# meetring_ic.net
KiCad netlist of a schematic drawn in EAGLE
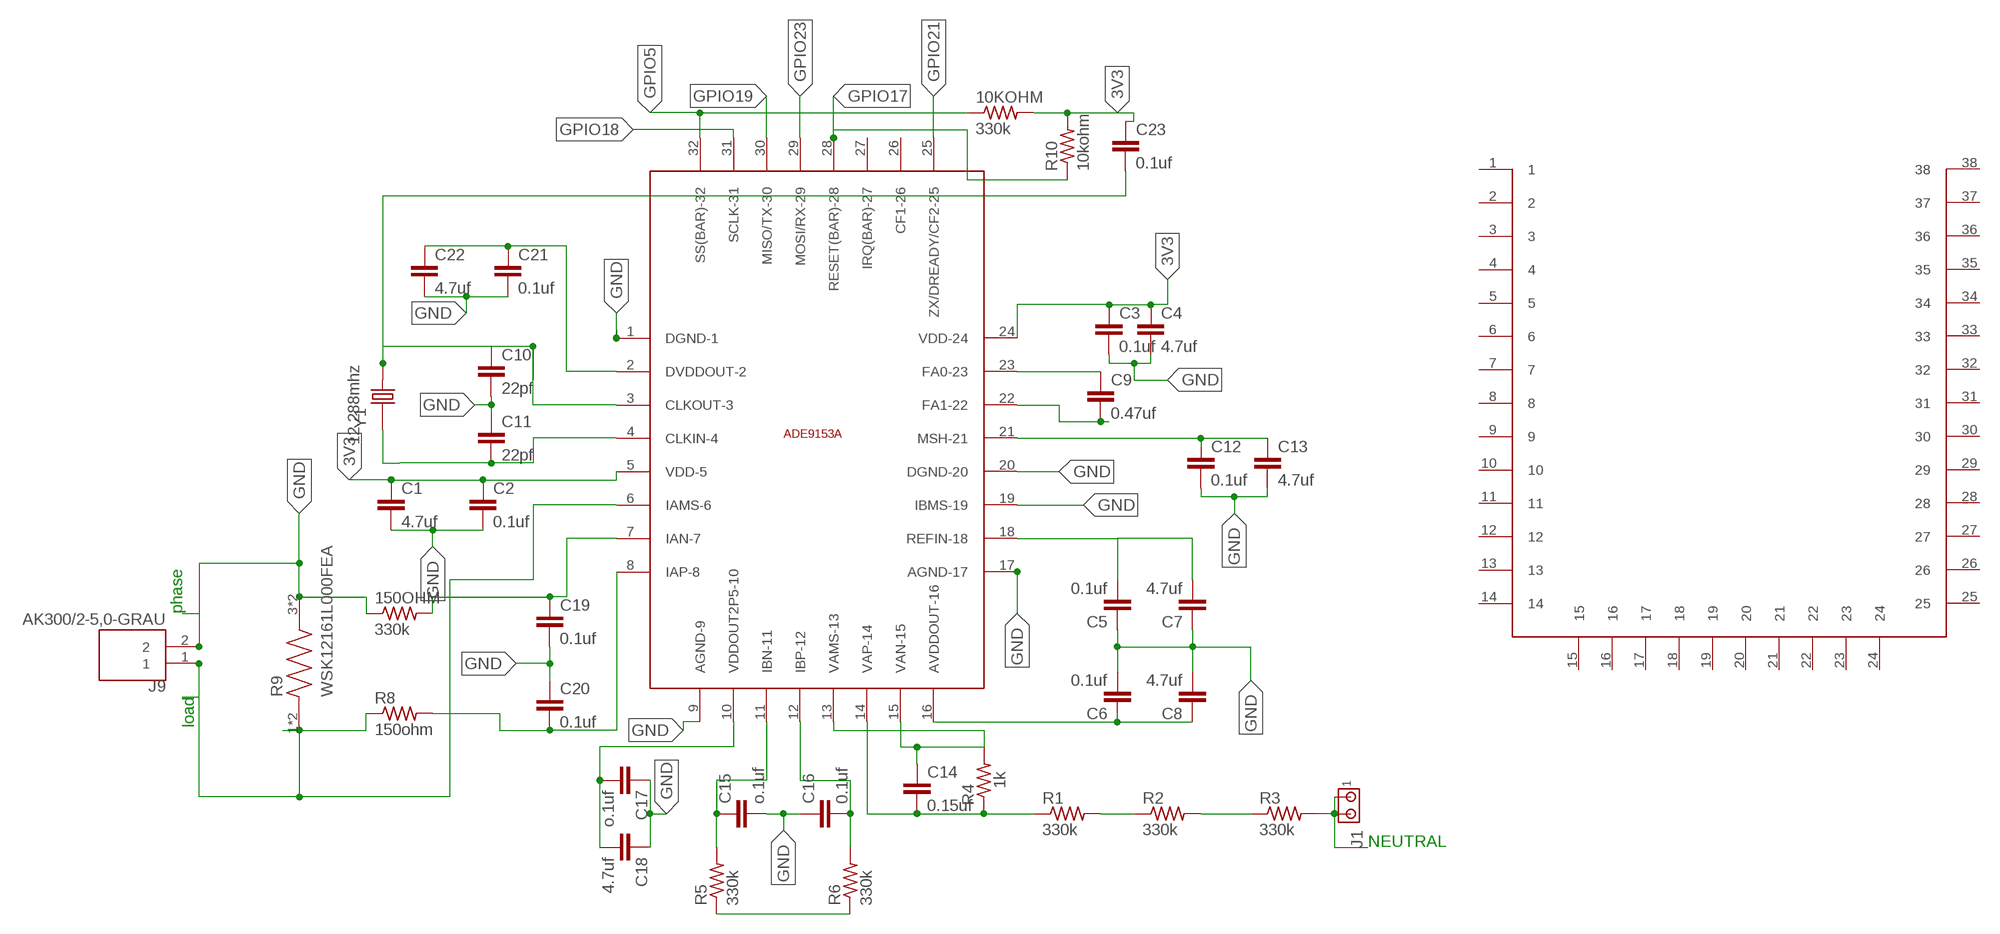
[diagram p0: schematic, sheet 1]

(export (version "E")
  (design (tool "Eeschema 10.0.6"))
  (components
    (comp (ref "10KOHM")
      (value "330k")
      (footprint "eagle-import:0204_7")
      (libsource (lib "eagle-import") (part "R-US_0204/7"))
    )
    (comp (ref "150OHM")
      (value "330k")
      (footprint "eagle-import:0204_7")
      (libsource (lib "eagle-import") (part "R-US_0204/7"))
    )
    (comp (ref "C1")
      (value "4.7uf")
      (footprint "eagle-import:C2.5-2")
      (libsource (lib "eagle-import") (part "C2.5/2"))
    )
    (comp (ref "C2")
      (value "0.1uf")
      (footprint "eagle-import:C2.5-2")
      (libsource (lib "eagle-import") (part "C2.5/2"))
    )
    (comp (ref "C3")
      (value "0.1uf")
      (footprint "eagle-import:C2.5-2")
      (libsource (lib "eagle-import") (part "C2.5/2"))
    )
    (comp (ref "C4")
      (value "4.7uf")
      (footprint "eagle-import:C2.5-2")
      (libsource (lib "eagle-import") (part "C2.5/2"))
    )
    (comp (ref "C5")
      (value "0.1uf")
      (footprint "eagle-import:C2.5-2")
      (libsource (lib "eagle-import") (part "C2.5/2"))
    )
    (comp (ref "C6")
      (value "0.1uf")
      (footprint "eagle-import:C2.5-2")
      (libsource (lib "eagle-import") (part "C2.5/2"))
    )
    (comp (ref "C7")
      (value "4.7uf")
      (footprint "eagle-import:C2.5-2")
      (libsource (lib "eagle-import") (part "C2.5/2"))
    )
    (comp (ref "C8")
      (value "4.7uf")
      (footprint "eagle-import:C2.5-2")
      (libsource (lib "eagle-import") (part "C2.5/2"))
    )
    (comp (ref "C9")
      (value "0.47uf")
      (footprint "eagle-import:C2.5-2")
      (libsource (lib "eagle-import") (part "C2.5/2"))
    )
    (comp (ref "C10")
      (value "22pf")
      (footprint "eagle-import:C2.5-2")
      (libsource (lib "eagle-import") (part "C2.5/2"))
    )
    (comp (ref "C11")
      (value "22pf")
      (footprint "eagle-import:C2.5-2")
      (libsource (lib "eagle-import") (part "C2.5/2"))
    )
    (comp (ref "C12")
      (value "0.1uf")
      (footprint "eagle-import:C2.5-2")
      (libsource (lib "eagle-import") (part "C2.5/2"))
    )
    (comp (ref "C13")
      (value "4.7uf")
      (footprint "eagle-import:C2.5-2")
      (libsource (lib "eagle-import") (part "C2.5/2"))
    )
    (comp (ref "C14")
      (value "0.15uf")
      (footprint "eagle-import:C2.5-2")
      (libsource (lib "eagle-import") (part "C2.5/2"))
    )
    (comp (ref "C15")
      (value "o.1uf")
      (footprint "eagle-import:C2.5-2")
      (libsource (lib "eagle-import") (part "C2.5/2"))
    )
    (comp (ref "C16")
      (value "0.1uf")
      (footprint "eagle-import:C2.5-2")
      (libsource (lib "eagle-import") (part "C2.5/2"))
    )
    (comp (ref "C17")
      (value "o.1uf")
      (footprint "eagle-import:C2.5-2")
      (libsource (lib "eagle-import") (part "C2.5/2"))
    )
    (comp (ref "C18")
      (value "4.7uf")
      (footprint "eagle-import:C2.5-2")
      (libsource (lib "eagle-import") (part "C2.5/2"))
    )
    (comp (ref "C19")
      (value "0.1uf")
      (footprint "eagle-import:C2.5-2")
      (libsource (lib "eagle-import") (part "C2.5/2"))
    )
    (comp (ref "C20")
      (value "0.1uf")
      (footprint "eagle-import:C2.5-2")
      (libsource (lib "eagle-import") (part "C2.5/2"))
    )
    (comp (ref "C21")
      (value "0.1uf")
      (footprint "eagle-import:C2.5-2")
      (libsource (lib "eagle-import") (part "C2.5/2"))
    )
    (comp (ref "C22")
      (value "4.7uf")
      (footprint "eagle-import:C2.5-2")
      (libsource (lib "eagle-import") (part "C2.5/2"))
    )
    (comp (ref "C23")
      (value "0.1uf")
      (footprint "eagle-import:C2.5-2")
      (libsource (lib "eagle-import") (part "C2.5/2"))
    )
    (comp (ref "J1")
      (value "MTA02-156")
      (footprint "eagle-import:1X2MTA")
      (libsource (lib "eagle-import") (part "MTA02-156"))
    )
    (comp (ref "J9")
      (value "AK300/2-5,0-GRAU")
      (footprint "eagle-import:PTR_AK300_2-5,0-GRAU")
      (fields (field (name "MF") "PTR Messtechnik"))
      (libsource (lib "eagle-import") (part "AK300/2-5,0-GRAU"))
    )
    (comp (ref "R1")
      (value "330k")
      (footprint "eagle-import:0204_7")
      (libsource (lib "eagle-import") (part "R-US_0204/7"))
    )
    (comp (ref "R2")
      (value "330k")
      (footprint "eagle-import:0204_7")
      (libsource (lib "eagle-import") (part "R-US_0204/7"))
    )
    (comp (ref "R3")
      (value "330k")
      (footprint "eagle-import:0204_7")
      (libsource (lib "eagle-import") (part "R-US_0204/7"))
    )
    (comp (ref "R4")
      (value "1k")
      (footprint "eagle-import:0204_7")
      (libsource (lib "eagle-import") (part "R-US_0204/7"))
    )
    (comp (ref "R5")
      (value "330k")
      (footprint "eagle-import:0204_7")
      (libsource (lib "eagle-import") (part "R-US_0204/7"))
    )
    (comp (ref "R6")
      (value "330k")
      (footprint "eagle-import:0204_7")
      (libsource (lib "eagle-import") (part "R-US_0204/7"))
    )
    (comp (ref "R8")
      (value "150ohm")
      (footprint "eagle-import:0204_7")
      (libsource (lib "eagle-import") (part "R-US_0204/7"))
    )
    (comp (ref "R9")
      (value "WSK12161L000FEA")
      (footprint "eagle-import:RES_WSK12161L000FEA")
      (fields (field (name "MF") "Vishay Intertechnology"))
      (libsource (lib "eagle-import") (part "WSK12161L000FEA"))
    )
    (comp (ref "R10")
      (value "10kohm")
      (footprint "eagle-import:0204_7")
      (libsource (lib "eagle-import") (part "R-US_0204/7"))
    )
    (comp (ref "U$1")
      (value "ADE9153A_BASEADE9153A_BASE")
      (footprint "eagle-import:ADE9153A_BASE")
      (libsource (lib "eagle-import") (part "ADE9153A_BASEADE9153A_BASE"))
    )
    (comp (ref "U$2")
      (value "LIB1OPTION_HOLE")
      (footprint "eagle-import:1X14MTA")
      (libsource (lib "eagle-import") (part "LIB1OPTION_HOLE"))
    )
    (comp (ref "Y1")
      (value "12.288mhz")
      (footprint "eagle-import:XTAL_ECS-200-20-1X")
      (fields (field (name "MF") "ECS International") (field (name "MP") "ECS-240.0001-18-1X"))
      (libsource (lib "eagle-import") (part "ECS-240.0001-18-1X"))
    )
  )
  (nets
    (net (code "1") (name "3V3") (class "Default")
      (node (ref "10KOHM") (pin "2") (pinfunction "2_2") (pintype "passive"))
      (node (ref "C1") (pin "1") (pinfunction "1_1") (pintype "passive"))
      (node (ref "C2") (pin "1") (pinfunction "1_1") (pintype "passive"))
      (node (ref "C23") (pin "1") (pinfunction "1_1") (pintype "passive"))
      (node (ref "C3") (pin "1") (pinfunction "1_1") (pintype "passive"))
      (node (ref "C4") (pin "1") (pinfunction "1_1") (pintype "passive"))
      (node (ref "R10") (pin "2") (pinfunction "2_2") (pintype "passive"))
      (node (ref "U$1") (pin "24") (pinfunction "VDD-24_24") (pintype "bidirectional"))
      (node (ref "U$1") (pin "5") (pinfunction "VDD-5_5") (pintype "bidirectional"))
    )
    (net (code "2") (name "GND") (class "Default")
      (node (ref "150OHM") (pin "1") (pinfunction "1_1") (pintype "passive"))
      (node (ref "C1") (pin "2") (pinfunction "2_2") (pintype "passive"))
      (node (ref "C10") (pin "2") (pinfunction "2_2") (pintype "passive"))
      (node (ref "C11") (pin "1") (pinfunction "1_1") (pintype "passive"))
      (node (ref "C12") (pin "2") (pinfunction "2_2") (pintype "passive"))
      (node (ref "C13") (pin "2") (pinfunction "2_2") (pintype "passive"))
      (node (ref "C15") (pin "2") (pinfunction "2_2") (pintype "passive"))
      (node (ref "C16") (pin "1") (pinfunction "1_1") (pintype "passive"))
      (node (ref "C17") (pin "1") (pinfunction "1_1") (pintype "passive"))
      (node (ref "C18") (pin "1") (pinfunction "1_1") (pintype "passive"))
      (node (ref "C19") (pin "2") (pinfunction "2_2") (pintype "passive"))
      (node (ref "C2") (pin "2") (pinfunction "2_2") (pintype "passive"))
      (node (ref "C20") (pin "1") (pinfunction "1_1") (pintype "passive"))
      (node (ref "C21") (pin "2") (pinfunction "2_2") (pintype "passive"))
      (node (ref "C22") (pin "2") (pinfunction "2_2") (pintype "passive"))
      (node (ref "C3") (pin "2") (pinfunction "2_2") (pintype "passive"))
      (node (ref "C4") (pin "2") (pinfunction "2_2") (pintype "passive"))
      (node (ref "C5") (pin "1") (pinfunction "1_1") (pintype "passive"))
      (node (ref "C6") (pin "2") (pinfunction "2_2") (pintype "passive"))
      (node (ref "C7") (pin "1") (pinfunction "1_1") (pintype "passive"))
      (node (ref "C8") (pin "2") (pinfunction "2_2") (pintype "passive"))
      (node (ref "J9") (pin "2") (pinfunction "2_2") (pintype "passive"))
      (node (ref "R9") (pin "3") (pinfunction "2_3") (pintype "passive"))
      (node (ref "R9") (pin "4") (pinfunction "2_4") (pintype "passive"))
      (node (ref "U$1") (pin "1") (pinfunction "DGND-1_1") (pintype "bidirectional"))
      (node (ref "U$1") (pin "17") (pinfunction "AGND-17_17") (pintype "bidirectional"))
      (node (ref "U$1") (pin "19") (pinfunction "IBMS-19_19") (pintype "bidirectional"))
      (node (ref "U$1") (pin "20") (pinfunction "DGND-20_20") (pintype "bidirectional"))
      (node (ref "U$1") (pin "9") (pinfunction "AGND-9_9") (pintype "bidirectional"))
    )
    (net (code "3") (name "GPIO5") (class "Default")
      (node (ref "10KOHM") (pin "1") (pinfunction "1_1") (pintype "passive"))
      (node (ref "U$1") (pin "32") (pinfunction "SS(BAR)-32_32") (pintype "bidirectional"))
    )
    (net (code "4") (name "GPIO17") (class "Default")
      (node (ref "R10") (pin "1") (pinfunction "1_1") (pintype "passive"))
      (node (ref "U$1") (pin "28") (pinfunction "RESET(BAR)-28_28") (pintype "bidirectional"))
    )
    (net (code "5") (name "GPIO18") (class "Default")
      (node (ref "U$1") (pin "31") (pinfunction "SCLK-31_31") (pintype "bidirectional"))
    )
    (net (code "6") (name "GPIO19") (class "Default")
      (node (ref "U$1") (pin "30") (pinfunction "MISO/TX-30_30") (pintype "bidirectional"))
    )
    (net (code "7") (name "GPIO21") (class "Default")
      (node (ref "U$1") (pin "25") (pinfunction "ZX/DREADY/CF2-25_25") (pintype "bidirectional"))
    )
    (net (code "8") (name "GPIO23") (class "Default")
      (node (ref "U$1") (pin "29") (pinfunction "MOSI/RX-29_29") (pintype "bidirectional"))
    )
    (net (code "9") (name "Net-(J1-Pad1)") (class "Default")
      (node (ref "J1") (pin "1") (pinfunction "1_1") (pintype "passive"))
      (node (ref "J1") (pin "2") (pinfunction "2_2") (pintype "passive"))
      (node (ref "R3") (pin "2") (pinfunction "2_2") (pintype "passive"))
    )
    (net (code "10") (name "Net-(R1-Pad2)") (class "Default")
      (node (ref "R1") (pin "2") (pinfunction "2_2") (pintype "passive"))
      (node (ref "R2") (pin "1") (pinfunction "1_1") (pintype "passive"))
    )
    (net (code "11") (name "Net-(R2-Pad2)") (class "Default")
      (node (ref "R2") (pin "2") (pinfunction "2_2") (pintype "passive"))
      (node (ref "R3") (pin "1") (pinfunction "1_1") (pintype "passive"))
    )
    (net (code "12") (name "Net-(R5-Pad1)") (class "Default")
      (node (ref "R5") (pin "1") (pinfunction "1_1") (pintype "passive"))
      (node (ref "R6") (pin "1") (pinfunction "1_1") (pintype "passive"))
    )
    (net (code "13") (name "Net-(U$1-AVDDOUT-16)") (class "Default")
      (node (ref "C6") (pin "1") (pinfunction "1_1") (pintype "passive"))
      (node (ref "C8") (pin "1") (pinfunction "1_1") (pintype "passive"))
      (node (ref "U$1") (pin "16") (pinfunction "AVDDOUT-16_16") (pintype "bidirectional"))
    )
    (net (code "14") (name "Net-(U$1-CLKIN-4)") (class "Default")
      (node (ref "C11") (pin "2") (pinfunction "2_2") (pintype "passive"))
      (node (ref "U$1") (pin "4") (pinfunction "CLKIN-4_4") (pintype "bidirectional"))
      (node (ref "Y1") (pin "1") (pinfunction "1_1") (pintype "passive"))
    )
    (net (code "15") (name "Net-(U$1-CLKOUT-3)") (class "Default")
      (node (ref "C10") (pin "1") (pinfunction "1_1") (pintype "passive"))
      (node (ref "C23") (pin "2") (pinfunction "2_2") (pintype "passive"))
      (node (ref "U$1") (pin "3") (pinfunction "CLKOUT-3_3") (pintype "bidirectional"))
      (node (ref "Y1") (pin "2") (pinfunction "2_2") (pintype "passive"))
    )
    (net (code "16") (name "Net-(U$1-DVDDOUT-2)") (class "Default")
      (node (ref "C21") (pin "1") (pinfunction "1_1") (pintype "passive"))
      (node (ref "C22") (pin "1") (pinfunction "1_1") (pintype "passive"))
      (node (ref "U$1") (pin "2") (pinfunction "DVDDOUT-2_2") (pintype "bidirectional"))
    )
    (net (code "17") (name "Net-(U$1-FA0-23)") (class "Default")
      (node (ref "C9") (pin "1") (pinfunction "1_1") (pintype "passive"))
      (node (ref "U$1") (pin "23") (pinfunction "FA0-23_23") (pintype "bidirectional"))
    )
    (net (code "18") (name "Net-(U$1-FA1-22)") (class "Default")
      (node (ref "C9") (pin "2") (pinfunction "2_2") (pintype "passive"))
      (node (ref "U$1") (pin "22") (pinfunction "FA1-22_22") (pintype "bidirectional"))
    )
    (net (code "19") (name "Net-(U$1-IAMS-6)") (class "Default")
      (node (ref "J9") (pin "1") (pinfunction "1_1") (pintype "passive"))
      (node (ref "R8") (pin "1") (pinfunction "1_1") (pintype "passive"))
      (node (ref "R9") (pin "1") (pinfunction "1_1") (pintype "passive"))
      (node (ref "R9") (pin "2") (pinfunction "1_2") (pintype "passive"))
      (node (ref "U$1") (pin "6") (pinfunction "IAMS-6_6") (pintype "bidirectional"))
    )
    (net (code "20") (name "Net-(U$1-IAN-7)") (class "Default")
      (node (ref "150OHM") (pin "2") (pinfunction "2_2") (pintype "passive"))
      (node (ref "C19") (pin "1") (pinfunction "1_1") (pintype "passive"))
      (node (ref "U$1") (pin "7") (pinfunction "IAN-7_7") (pintype "bidirectional"))
    )
    (net (code "21") (name "Net-(U$1-IAP-8)") (class "Default")
      (node (ref "C20") (pin "2") (pinfunction "2_2") (pintype "passive"))
      (node (ref "R8") (pin "2") (pinfunction "2_2") (pintype "passive"))
      (node (ref "U$1") (pin "8") (pinfunction "IAP-8_8") (pintype "bidirectional"))
    )
    (net (code "22") (name "Net-(U$1-IBN-11)") (class "Default")
      (node (ref "C15") (pin "1") (pinfunction "1_1") (pintype "passive"))
      (node (ref "R5") (pin "2") (pinfunction "2_2") (pintype "passive"))
      (node (ref "U$1") (pin "11") (pinfunction "IBN-11_11") (pintype "bidirectional"))
    )
    (net (code "23") (name "Net-(U$1-IBP-12)") (class "Default")
      (node (ref "C16") (pin "2") (pinfunction "2_2") (pintype "passive"))
      (node (ref "R6") (pin "2") (pinfunction "2_2") (pintype "passive"))
      (node (ref "U$1") (pin "12") (pinfunction "IBP-12_12") (pintype "bidirectional"))
    )
    (net (code "24") (name "Net-(U$1-MSH-21)") (class "Default")
      (node (ref "C12") (pin "1") (pinfunction "1_1") (pintype "passive"))
      (node (ref "C13") (pin "1") (pinfunction "1_1") (pintype "passive"))
      (node (ref "U$1") (pin "21") (pinfunction "MSH-21_21") (pintype "bidirectional"))
    )
    (net (code "25") (name "Net-(U$1-REFIN-18)") (class "Default")
      (node (ref "C5") (pin "2") (pinfunction "2_2") (pintype "passive"))
      (node (ref "C7") (pin "2") (pinfunction "2_2") (pintype "passive"))
      (node (ref "U$1") (pin "18") (pinfunction "REFIN-18_18") (pintype "bidirectional"))
    )
    (net (code "26") (name "Net-(U$1-VAMS-13)") (class "Default")
      (node (ref "C14") (pin "1") (pinfunction "1_1") (pintype "passive"))
      (node (ref "R4") (pin "2") (pinfunction "2_2") (pintype "passive"))
      (node (ref "U$1") (pin "13") (pinfunction "VAMS-13_13") (pintype "bidirectional"))
      (node (ref "U$1") (pin "15") (pinfunction "VAN-15_15") (pintype "bidirectional"))
    )
    (net (code "27") (name "Net-(U$1-VAP-14)") (class "Default")
      (node (ref "C14") (pin "2") (pinfunction "2_2") (pintype "passive"))
      (node (ref "R1") (pin "1") (pinfunction "1_1") (pintype "passive"))
      (node (ref "R4") (pin "1") (pinfunction "1_1") (pintype "passive"))
      (node (ref "U$1") (pin "14") (pinfunction "VAP-14_14") (pintype "bidirectional"))
    )
    (net (code "28") (name "Net-(U$1-VDDOUT2P5-10)") (class "Default")
      (node (ref "C17") (pin "2") (pinfunction "2_2") (pintype "passive"))
      (node (ref "C18") (pin "2") (pinfunction "2_2") (pintype "passive"))
      (node (ref "U$1") (pin "10") (pinfunction "VDDOUT2P5-10_10") (pintype "bidirectional"))
    )
    (net (code "29") (name "unconnected-(U$1-CF1-26-Pad26)") (class "Default")
      (node (ref "U$1") (pin "26") (pinfunction "CF1-26_26") (pintype "bidirectional"))
    )
    (net (code "30") (name "unconnected-(U$1-IRQ(BAR)-27-Pad27)") (class "Default")
      (node (ref "U$1") (pin "27") (pinfunction "IRQ(BAR)-27_27") (pintype "bidirectional"))
    )
    (net (code "31") (name "unconnected-(U$2-Pad1)") (class "Default")
      (node (ref "U$2") (pin "1") (pinfunction "1_1") (pintype "bidirectional"))
    )
    (net (code "32") (name "unconnected-(U$2-Pad2)") (class "Default")
      (node (ref "U$2") (pin "2") (pinfunction "2_2") (pintype "bidirectional"))
    )
    (net (code "33") (name "unconnected-(U$2-Pad3)") (class "Default")
      (node (ref "U$2") (pin "3") (pinfunction "3_3") (pintype "bidirectional"))
    )
    (net (code "34") (name "unconnected-(U$2-Pad4)") (class "Default")
      (node (ref "U$2") (pin "4") (pinfunction "4_4") (pintype "bidirectional"))
    )
    (net (code "35") (name "unconnected-(U$2-Pad5)") (class "Default")
      (node (ref "U$2") (pin "5") (pinfunction "5_5") (pintype "bidirectional"))
    )
    (net (code "36") (name "unconnected-(U$2-Pad6)") (class "Default")
      (node (ref "U$2") (pin "6") (pinfunction "6_6") (pintype "bidirectional"))
    )
    (net (code "37") (name "unconnected-(U$2-Pad7)") (class "Default")
      (node (ref "U$2") (pin "7") (pinfunction "7_7") (pintype "bidirectional"))
    )
    (net (code "38") (name "unconnected-(U$2-Pad8)") (class "Default")
      (node (ref "U$2") (pin "8") (pinfunction "8_8") (pintype "bidirectional"))
    )
    (net (code "39") (name "unconnected-(U$2-Pad9)") (class "Default")
      (node (ref "U$2") (pin "9") (pinfunction "9_9") (pintype "bidirectional"))
    )
    (net (code "40") (name "unconnected-(U$2-Pad10)") (class "Default")
      (node (ref "U$2") (pin "10") (pinfunction "10_10") (pintype "bidirectional"))
    )
    (net (code "41") (name "unconnected-(U$2-Pad11)") (class "Default")
      (node (ref "U$2") (pin "11") (pinfunction "11_11") (pintype "bidirectional"))
    )
    (net (code "42") (name "unconnected-(U$2-Pad12)") (class "Default")
      (node (ref "U$2") (pin "12") (pinfunction "12_12") (pintype "bidirectional"))
    )
    (net (code "43") (name "unconnected-(U$2-Pad13)") (class "Default")
      (node (ref "U$2") (pin "13") (pinfunction "13_13") (pintype "bidirectional"))
    )
    (net (code "44") (name "unconnected-(U$2-Pad14)") (class "Default")
      (node (ref "U$2") (pin "14") (pinfunction "14_14") (pintype "bidirectional"))
    )
    (net (code "45") (name "unconnected-(U$2-Pad15)") (class "Default")
      (node (ref "U$2") (pin "15") (pinfunction "15_15") (pintype "bidirectional"))
    )
    (net (code "46") (name "unconnected-(U$2-Pad16)") (class "Default")
      (node (ref "U$2") (pin "16") (pinfunction "16_16") (pintype "bidirectional"))
    )
    (net (code "47") (name "unconnected-(U$2-Pad17)") (class "Default")
      (node (ref "U$2") (pin "17") (pinfunction "17_17") (pintype "bidirectional"))
    )
    (net (code "48") (name "unconnected-(U$2-Pad18)") (class "Default")
      (node (ref "U$2") (pin "18") (pinfunction "18_18") (pintype "bidirectional"))
    )
    (net (code "49") (name "unconnected-(U$2-Pad19)") (class "Default")
      (node (ref "U$2") (pin "19") (pinfunction "19_19") (pintype "bidirectional"))
    )
    (net (code "50") (name "unconnected-(U$2-Pad20)") (class "Default")
      (node (ref "U$2") (pin "20") (pinfunction "20_20") (pintype "bidirectional"))
    )
    (net (code "51") (name "unconnected-(U$2-Pad21)") (class "Default")
      (node (ref "U$2") (pin "21") (pinfunction "21_21") (pintype "bidirectional"))
    )
    (net (code "52") (name "unconnected-(U$2-Pad22)") (class "Default")
      (node (ref "U$2") (pin "22") (pinfunction "22_22") (pintype "bidirectional"))
    )
    (net (code "53") (name "unconnected-(U$2-Pad23)") (class "Default")
      (node (ref "U$2") (pin "23") (pinfunction "23_23") (pintype "bidirectional"))
    )
    (net (code "54") (name "unconnected-(U$2-Pad24)") (class "Default")
      (node (ref "U$2") (pin "24") (pinfunction "24_24") (pintype "bidirectional"))
    )
    (net (code "55") (name "unconnected-(U$2-Pad25)") (class "Default")
      (node (ref "U$2") (pin "25") (pinfunction "25_25") (pintype "bidirectional"))
    )
    (net (code "56") (name "unconnected-(U$2-Pad26)") (class "Default")
      (node (ref "U$2") (pin "26") (pinfunction "26_26") (pintype "bidirectional"))
    )
    (net (code "57") (name "unconnected-(U$2-Pad27)") (class "Default")
      (node (ref "U$2") (pin "27") (pinfunction "27_27") (pintype "bidirectional"))
    )
    (net (code "58") (name "unconnected-(U$2-Pad28)") (class "Default")
      (node (ref "U$2") (pin "28") (pinfunction "28_28") (pintype "bidirectional"))
    )
    (net (code "59") (name "unconnected-(U$2-Pad29)") (class "Default")
      (node (ref "U$2") (pin "29") (pinfunction "29_29") (pintype "bidirectional"))
    )
    (net (code "60") (name "unconnected-(U$2-Pad30)") (class "Default")
      (node (ref "U$2") (pin "30") (pinfunction "30_30") (pintype "bidirectional"))
    )
    (net (code "61") (name "unconnected-(U$2-Pad31)") (class "Default")
      (node (ref "U$2") (pin "31") (pinfunction "31_31") (pintype "bidirectional"))
    )
    (net (code "62") (name "unconnected-(U$2-Pad32)") (class "Default")
      (node (ref "U$2") (pin "32") (pinfunction "32_32") (pintype "bidirectional"))
    )
    (net (code "63") (name "unconnected-(U$2-Pad33)") (class "Default")
      (node (ref "U$2") (pin "33") (pinfunction "33_33") (pintype "bidirectional"))
    )
    (net (code "64") (name "unconnected-(U$2-Pad34)") (class "Default")
      (node (ref "U$2") (pin "34") (pinfunction "34_34") (pintype "bidirectional"))
    )
    (net (code "65") (name "unconnected-(U$2-Pad35)") (class "Default")
      (node (ref "U$2") (pin "35") (pinfunction "35_35") (pintype "bidirectional"))
    )
    (net (code "66") (name "unconnected-(U$2-Pad36)") (class "Default")
      (node (ref "U$2") (pin "36") (pinfunction "36_36") (pintype "bidirectional"))
    )
    (net (code "67") (name "unconnected-(U$2-Pad37)") (class "Default")
      (node (ref "U$2") (pin "37") (pinfunction "37_37") (pintype "bidirectional"))
    )
    (net (code "68") (name "unconnected-(U$2-Pad38)") (class "Default")
      (node (ref "U$2") (pin "38") (pinfunction "38_38") (pintype "bidirectional"))
    )
  )
)
